# MCU_STM32F427ZGT6.net
KiCad netlist of a schematic drawn in Altium Designer
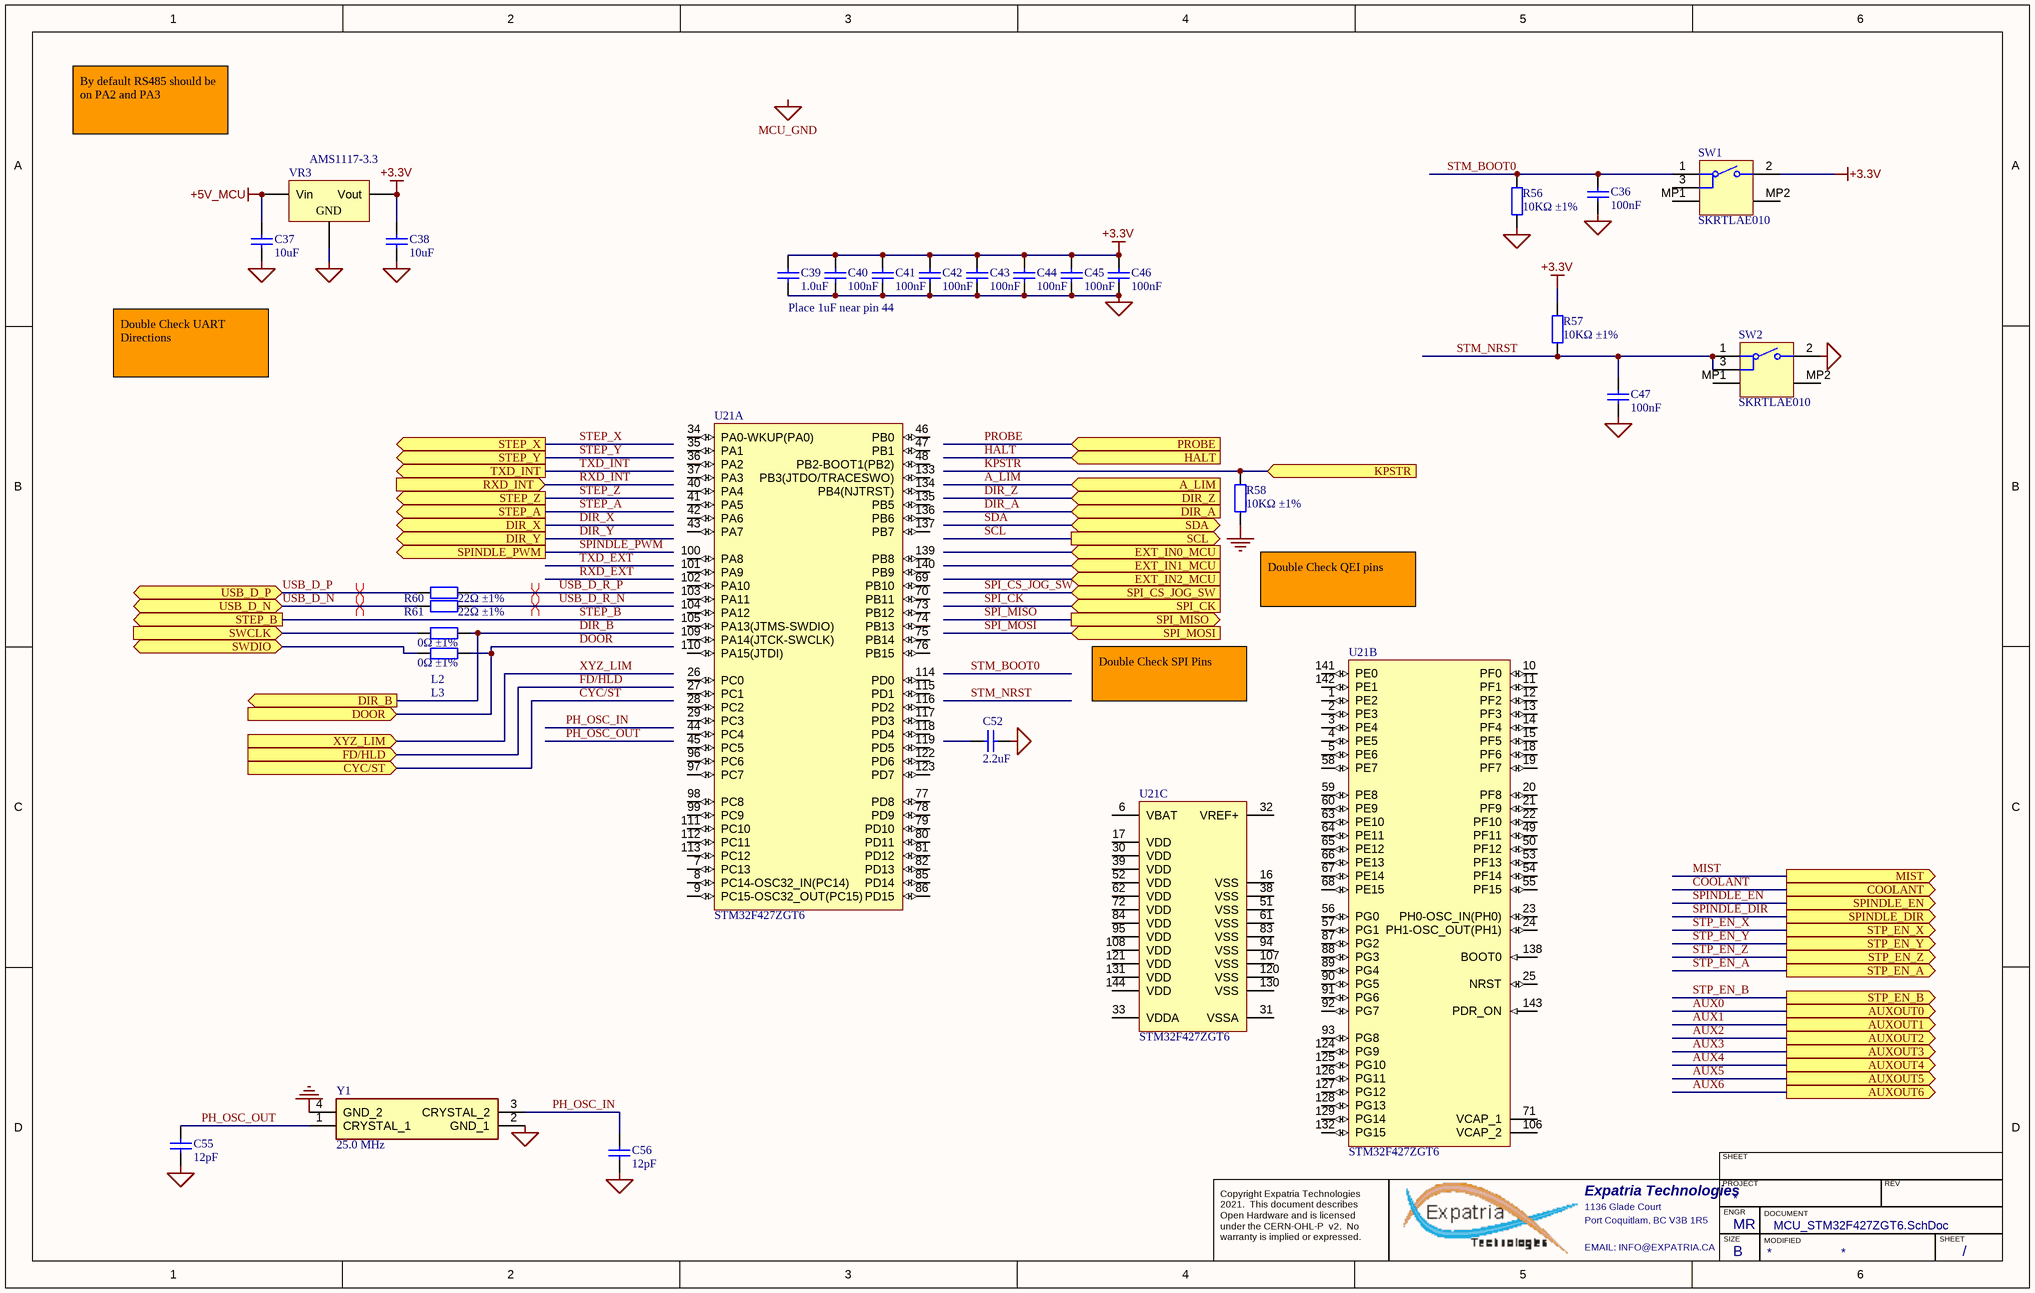
[diagram p0: MCU_STM32F427ZGT6.SchDoc]

(export (version "E")
  (design (tool "Eeschema 10.0.6"))
  (components
    (comp (ref "C36")
      (value "100nF")
      (footprint "0402_C")
      (description "Chip capacitors")
      (fields
        (field (name "MANUFACTURER") "Samsung Electro-Mechanics")
        (field (name "PARTNUMBER") "CL05B104KO5NNNC")
      )
      (libsource (lib "Cap") (part "0402 100nF (104) 10% 16V"))
    )
    (comp (ref "C37")
      (value "10uF")
      (footprint "1206_C")
      (description "Chip capacitors")
      (fields
        (field (name "MANUFACTURER") "Samsung Electro-Mechanics")
        (field (name "PARTNUMBER") "CL31A106KBHNNNE")
      )
      (libsource (lib "Cap") (part "1206 10uF (106) 10% 50V"))
    )
    (comp (ref "C38")
      (value "10uF")
      (footprint "1206_C")
      (description "Chip capacitors")
      (fields
        (field (name "MANUFACTURER") "Samsung Electro-Mechanics")
        (field (name "PARTNUMBER") "CL31A106KBHNNNE")
      )
      (libsource (lib "Cap") (part "1206 10uF (106) 10% 50V"))
    )
    (comp (ref "C39")
      (value "1.0uF")
      (footprint "0402_C")
      (description "Chip capacitor")
      (fields
        (field (name "MANUFACTURER") "Samsung Electro-Mechanics")
        (field (name "PARTNUMBER") "CL05A105KA5NQNC")
      )
      (libsource (lib "Cap") (part "0402 1.0uF (105) 10% 25V"))
    )
    (comp (ref "C40")
      (value "100nF")
      (footprint "0402_C")
      (description "Chip capacitors")
      (fields
        (field (name "MANUFACTURER") "Samsung Electro-Mechanics")
        (field (name "PARTNUMBER") "CL05B104KO5NNNC")
      )
      (libsource (lib "Cap") (part "0402 100nF (104) 10% 16V"))
    )
    (comp (ref "C41")
      (value "100nF")
      (footprint "0402_C")
      (description "Chip capacitors")
      (fields
        (field (name "MANUFACTURER") "Samsung Electro-Mechanics")
        (field (name "PARTNUMBER") "CL05B104KO5NNNC")
      )
      (libsource (lib "Cap") (part "0402 100nF (104) 10% 16V"))
    )
    (comp (ref "C42")
      (value "100nF")
      (footprint "0402_C")
      (description "Chip capacitors")
      (fields
        (field (name "MANUFACTURER") "Samsung Electro-Mechanics")
        (field (name "PARTNUMBER") "CL05B104KO5NNNC")
      )
      (libsource (lib "Cap") (part "0402 100nF (104) 10% 16V"))
    )
    (comp (ref "C43")
      (value "100nF")
      (footprint "0402_C")
      (description "Chip capacitors")
      (fields
        (field (name "MANUFACTURER") "Samsung Electro-Mechanics")
        (field (name "PARTNUMBER") "CL05B104KO5NNNC")
      )
      (libsource (lib "Cap") (part "0402 100nF (104) 10% 16V"))
    )
    (comp (ref "C44")
      (value "100nF")
      (footprint "0402_C")
      (description "Chip capacitors")
      (fields
        (field (name "MANUFACTURER") "Samsung Electro-Mechanics")
        (field (name "PARTNUMBER") "CL05B104KO5NNNC")
      )
      (libsource (lib "Cap") (part "0402 100nF (104) 10% 16V"))
    )
    (comp (ref "C45")
      (value "100nF")
      (footprint "0402_C")
      (description "Chip capacitors")
      (fields
        (field (name "MANUFACTURER") "Samsung Electro-Mechanics")
        (field (name "PARTNUMBER") "CL05B104KO5NNNC")
      )
      (libsource (lib "Cap") (part "0402 100nF (104) 10% 16V"))
    )
    (comp (ref "C46")
      (value "100nF")
      (footprint "0402_C")
      (description "Chip capacitors")
      (fields
        (field (name "MANUFACTURER") "Samsung Electro-Mechanics")
        (field (name "PARTNUMBER") "CL05B104KO5NNNC")
      )
      (libsource (lib "Cap") (part "0402 100nF (104) 10% 16V"))
    )
    (comp (ref "C47")
      (value "100nF")
      (footprint "0402_C")
      (description "Chip capacitors")
      (fields
        (field (name "MANUFACTURER") "Samsung Electro-Mechanics")
        (field (name "PARTNUMBER") "CL05B104KO5NNNC")
      )
      (libsource (lib "Cap") (part "0402 100nF (104) 10% 16V"))
    )
    (comp (ref "C52")
      (value "2.2uF")
      (footprint "0603_C")
      (description "Chip capacitors")
      (fields
        (field (name "MANUFACTURER") "Samsung Electro-Mechanics")
        (field (name "PARTNUMBER") "CL10A225KO8NNNC")
      )
      (libsource (lib "Cap") (part "0603 2.2uF (225) 10% 16V"))
    )
    (comp (ref "C55")
      (value "12pF")
      (footprint "0402_C")
      (description "Chip capacitors")
      (fields
        (field (name "MANUFACTURER") "Guangdong Fenghua Advanced Tech")
        (field (name "PARTNUMBER") "0402CG120J500NT")
      )
      (libsource (lib "Cap") (part "0402 12pF (120) 5% 50V"))
    )
    (comp (ref "C56")
      (value "12pF")
      (footprint "0402_C")
      (description "Chip capacitors")
      (fields
        (field (name "MANUFACTURER") "Guangdong Fenghua Advanced Tech")
        (field (name "PARTNUMBER") "0402CG120J500NT")
      )
      (libsource (lib "Cap") (part "0402 12pF (120) 5% 50V"))
    )
    (comp (ref "L2")
      (value "0Ω ±1%")
      (footprint "0402_R")
      (description "Chip resistor")
      (fields (field (name "POWER") "1/16W") (field (name "MANUFACTURER") "Uniroyal Elec"))
      (libsource (lib "PrintNC_GRBLHAL_Breakout") (part "0402 0R (0R0) 1%"))
    )
    (comp (ref "L3")
      (value "0Ω ±1%")
      (footprint "0402_R")
      (description "Chip resistor")
      (fields (field (name "POWER") "1/16W") (field (name "MANUFACTURER") "Uniroyal Elec"))
      (libsource (lib "PrintNC_GRBLHAL_Breakout") (part "0402 0R (0R0) 1%"))
    )
    (comp (ref "R56")
      (value "10KΩ ±1%")
      (footprint "0402_R")
      (description "Chip resistor")
      (fields (field (name "MANUFACTURER") "Uniroyal Elec") (field (name "PARTNUMBER") "0402WGF1002TCE"))
      (libsource (lib "RES") (part "0402 10K (1002) 1%"))
    )
    (comp (ref "R57")
      (value "10KΩ ±1%")
      (footprint "0402_R")
      (description "Chip resistor")
      (fields (field (name "MANUFACTURER") "Uniroyal Elec") (field (name "PARTNUMBER") "0402WGF1002TCE"))
      (libsource (lib "RES") (part "0402 10K (1002) 1%"))
    )
    (comp (ref "R58")
      (value "10KΩ ±1%")
      (footprint "0402_R")
      (description "Chip resistor")
      (fields (field (name "MANUFACTURER") "Uniroyal Elec") (field (name "PARTNUMBER") "0402WGF1002TCE"))
      (libsource (lib "") (part "0402 10K (1002) 1%_1"))
    )
    (comp (ref "R60")
      (value "22Ω ±1%")
      (footprint "0402_R")
      (description "Chip resistor")
      (fields (field (name "MANUFACTURER") "Uniroyal Elec") (field (name "PARTNUMBER") "0402WGF220JTCE"))
      (libsource (lib "RES") (part "0402 22R (22R0) 1%"))
    )
    (comp (ref "R61")
      (value "22Ω ±1%")
      (footprint "0402_R")
      (description "Chip resistor")
      (fields (field (name "MANUFACTURER") "Uniroyal Elec") (field (name "PARTNUMBER") "0402WGF220JTCE"))
      (libsource (lib "RES") (part "0402 22R (22R0) 1%"))
    )
    (comp (ref "SW1")
      (value "SKRTLAE010")
      (footprint "ALPS-SKRTLAE010_V")
      (description "Side Push Type, 250 V, -40 to 90 degC, 3-Pin SMD, RoHS, Tape and Reel")
      (fields (field (name "MANUFACTURER") "ALPS"))
      (libsource (lib "Altium Content Vault") (part "SW_SPST-3_A"))
    )
    (comp (ref "SW2")
      (value "SKRTLAE010")
      (footprint "ALPS-SKRTLAE010_V")
      (description "Side Push Type, 250 V, -40 to 90 degC, 3-Pin SMD, RoHS, Tape and Reel")
      (fields (field (name "MANUFACTURER") "ALPS"))
      (libsource (lib "Altium Content Vault") (part "SW_SPST-3_A"))
    )
    (comp (ref "U21")
      (value "STM32F427ZGT6")
      (footprint "STM-LQFP144_V")
      (fields (field (name "MANUFACTURER") "STMicroelectronics"))
      (libsource (lib "Altium Content Vault") (part "MC-ARM-STM32F427-SQ144"))
    )
    (comp (ref "VR3")
      (value "AMS1117-3.3")
      (footprint "SOT-223")
      (description "低压差线性稳压(LDO)")
      (libsource (lib "LDO") (part "SOT-223 AMS1117-3.3"))
    )
    (comp (ref "Y1")
      (value "25.0 MHz")
      (footprint "SamacSys:YSX321SL")
      (description "Crystal or Oscillator")
      (fields (field (name "MANUFACTURER_PART_NUMBER") "X322525MSB4SI"))
      (libsource (lib "*") (part "YSX321SL"))
    )
  )
  (nets
    (net (code "1") (name "+3.3V") (class "Default")
      (node (ref "C38") (pin "2") (pinfunction "2_2") (pintype "passive"))
      (node (ref "C39") (pin "2") (pinfunction "2_2") (pintype "passive"))
      (node (ref "C40") (pin "2") (pinfunction "2_2") (pintype "passive"))
      (node (ref "C41") (pin "2") (pinfunction "2_2") (pintype "passive"))
      (node (ref "C42") (pin "2") (pinfunction "2_2") (pintype "passive"))
      (node (ref "C43") (pin "2") (pinfunction "2_2") (pintype "passive"))
      (node (ref "C44") (pin "2") (pinfunction "2_2") (pintype "passive"))
      (node (ref "C45") (pin "2") (pinfunction "2_2") (pintype "passive"))
      (node (ref "C46") (pin "2") (pinfunction "2_2") (pintype "passive"))
      (node (ref "R57") (pin "1") (pinfunction "1_1") (pintype "passive"))
      (node (ref "SW1") (pin "2") (pinfunction "2_2") (pintype "passive"))
      (node (ref "VR3") (pin "2") (pinfunction "Vout_2") (pintype "passive"))
    )
    (net (code "2") (name "+5V_MCU") (class "Default")
      (node (ref "C37") (pin "2") (pinfunction "2_2") (pintype "passive"))
      (node (ref "VR3") (pin "3") (pinfunction "Vin_3") (pintype "passive"))
    )
    (net (code "14") (name "/DIR_B") (class "Default")
      (node (ref "L2") (pin "2") (pinfunction "2_2") (pintype "passive"))
    )
    (net (code "18") (name "/DOOR") (class "Default")
      (node (ref "L3") (pin "2") (pinfunction "2_2") (pintype "passive"))
    )
    (net (code "24") (name "/KPSTR") (class "Default")
      (node (ref "R58") (pin "2") (pinfunction "2_2") (pintype "passive"))
    )
    (net (code "26") (name "/PH_OSC_IN") (class "Default")
      (node (ref "C56") (pin "2") (pinfunction "2_2") (pintype "passive"))
      (node (ref "Y1") (pin "3") (pinfunction "CRYSTAL_2_3") (pintype "passive"))
    )
    (net (code "27") (name "/PH_OSC_OUT") (class "Default")
      (node (ref "C55") (pin "2") (pinfunction "2_2") (pintype "passive"))
      (node (ref "Y1") (pin "1") (pinfunction "CRYSTAL_1_1") (pintype "passive"))
    )
    (net (code "45") (name "/STM_BOOT0") (class "Default")
      (node (ref "C36") (pin "2") (pinfunction "2_2") (pintype "passive"))
      (node (ref "R56") (pin "1") (pinfunction "1_1") (pintype "passive"))
      (node (ref "SW1") (pin "1") (pinfunction "1_1") (pintype "passive"))
    )
    (net (code "46") (name "/STM_NRST") (class "Default")
      (node (ref "C47") (pin "2") (pinfunction "2_2") (pintype "passive"))
      (node (ref "R57") (pin "2") (pinfunction "2_2") (pintype "passive"))
      (node (ref "SW2") (pin "1") (pinfunction "1_1") (pintype "passive"))
      (node (ref "SW2") (pin "3") (pinfunction "3_3") (pintype "passive"))
    )
    (net (code "52") (name "/SWCLK") (class "Default")
      (node (ref "L2") (pin "1") (pinfunction "1_1") (pintype "passive"))
    )
    (net (code "53") (name "/SWDIO") (class "Default")
      (node (ref "L3") (pin "1") (pinfunction "1_1") (pintype "passive"))
    )
    (net (code "56") (name "/USB_D_N") (class "Default")
      (node (ref "R61") (pin "2") (pinfunction "2_2") (pintype "passive"))
    )
    (net (code "57") (name "/USB_D_P") (class "Default")
      (node (ref "R60") (pin "2") (pinfunction "2_2") (pintype "passive"))
    )
    (net (code "58") (name "/USB_D_R_N") (class "Default")
      (node (ref "R61") (pin "1") (pinfunction "1_1") (pintype "passive"))
    )
    (net (code "59") (name "/USB_D_R_P") (class "Default")
      (node (ref "R60") (pin "1") (pinfunction "1_1") (pintype "passive"))
    )
    (net (code "61") (name "GND") (class "Default")
      (node (ref "R58") (pin "1") (pinfunction "1_1") (pintype "passive"))
      (node (ref "Y1") (pin "4") (pinfunction "GND_2_4") (pintype "passive"))
    )
    (net (code "62") (name "MCU_GND") (class "Default")
      (node (ref "C36") (pin "1") (pinfunction "1_1") (pintype "passive"))
      (node (ref "C37") (pin "1") (pinfunction "1_1") (pintype "passive"))
      (node (ref "C38") (pin "1") (pinfunction "1_1") (pintype "passive"))
      (node (ref "C39") (pin "1") (pinfunction "1_1") (pintype "passive"))
      (node (ref "C40") (pin "1") (pinfunction "1_1") (pintype "passive"))
      (node (ref "C41") (pin "1") (pinfunction "1_1") (pintype "passive"))
      (node (ref "C42") (pin "1") (pinfunction "1_1") (pintype "passive"))
      (node (ref "C43") (pin "1") (pinfunction "1_1") (pintype "passive"))
      (node (ref "C44") (pin "1") (pinfunction "1_1") (pintype "passive"))
      (node (ref "C45") (pin "1") (pinfunction "1_1") (pintype "passive"))
      (node (ref "C46") (pin "1") (pinfunction "1_1") (pintype "passive"))
      (node (ref "C47") (pin "1") (pinfunction "1_1") (pintype "passive"))
      (node (ref "C52") (pin "1") (pinfunction "1_1") (pintype "passive"))
      (node (ref "C55") (pin "1") (pinfunction "1_1") (pintype "passive"))
      (node (ref "C56") (pin "1") (pinfunction "1_1") (pintype "passive"))
      (node (ref "R56") (pin "2") (pinfunction "2_2") (pintype "passive"))
      (node (ref "SW2") (pin "2") (pinfunction "2_2") (pintype "passive"))
      (node (ref "VR3") (pin "1") (pinfunction "GND_1") (pintype "passive"))
      (node (ref "Y1") (pin "2") (pinfunction "GND_1_2") (pintype "passive"))
    )
    (net (code "63") (name "unconnected-(C52-Pad2)") (class "Default")
      (node (ref "C52") (pin "2") (pinfunction "2_2") (pintype "passive"))
    )
    (net (code "64") (name "unconnected-(SW1-Pad3)") (class "Default")
      (node (ref "SW1") (pin "3") (pinfunction "3_3") (pintype "passive"))
    )
    (net (code "65") (name "unconnected-(SW1-PadMP1)") (class "Default")
      (node (ref "SW1") (pin "MP1") (pinfunction "MP1_MP1") (pintype "passive"))
    )
    (net (code "66") (name "unconnected-(SW1-PadMP2)") (class "Default")
      (node (ref "SW1") (pin "MP2") (pinfunction "MP2_MP2") (pintype "passive"))
    )
    (net (code "67") (name "unconnected-(SW2-PadMP1)") (class "Default")
      (node (ref "SW2") (pin "MP1") (pinfunction "MP1_MP1") (pintype "passive"))
    )
    (net (code "68") (name "unconnected-(SW2-PadMP2)") (class "Default")
      (node (ref "SW2") (pin "MP2") (pinfunction "MP2_MP2") (pintype "passive"))
    )
    (net (code "69") (name "unconnected-(U21A-PA0-WKUP(PA0)-Pad34)") (class "Default")
      (node (ref "U21") (pin "34") (pinfunction "PA0-WKUP(PA0)_34") (pintype "bidirectional"))
    )
    (net (code "70") (name "unconnected-(U21A-PA1-Pad35)") (class "Default")
      (node (ref "U21") (pin "35") (pinfunction "PA1_35") (pintype "bidirectional"))
    )
    (net (code "71") (name "unconnected-(U21A-PA2-Pad36)") (class "Default")
      (node (ref "U21") (pin "36") (pinfunction "PA2_36") (pintype "bidirectional"))
    )
    (net (code "72") (name "unconnected-(U21A-PA3-Pad37)") (class "Default")
      (node (ref "U21") (pin "37") (pinfunction "PA3_37") (pintype "bidirectional"))
    )
    (net (code "73") (name "unconnected-(U21A-PA4-Pad40)") (class "Default")
      (node (ref "U21") (pin "40") (pinfunction "PA4_40") (pintype "bidirectional"))
    )
    (net (code "74") (name "unconnected-(U21A-PA5-Pad41)") (class "Default")
      (node (ref "U21") (pin "41") (pinfunction "PA5_41") (pintype "bidirectional"))
    )
    (net (code "75") (name "unconnected-(U21A-PA6-Pad42)") (class "Default")
      (node (ref "U21") (pin "42") (pinfunction "PA6_42") (pintype "bidirectional"))
    )
    (net (code "76") (name "unconnected-(U21A-PA7-Pad43)") (class "Default")
      (node (ref "U21") (pin "43") (pinfunction "PA7_43") (pintype "bidirectional"))
    )
    (net (code "77") (name "unconnected-(U21A-PA8-Pad100)") (class "Default")
      (node (ref "U21") (pin "100") (pinfunction "PA8_100") (pintype "bidirectional"))
    )
    (net (code "78") (name "unconnected-(U21A-PA9-Pad101)") (class "Default")
      (node (ref "U21") (pin "101") (pinfunction "PA9_101") (pintype "bidirectional"))
    )
    (net (code "79") (name "unconnected-(U21A-PA10-Pad102)") (class "Default")
      (node (ref "U21") (pin "102") (pinfunction "PA10_102") (pintype "bidirectional"))
    )
    (net (code "80") (name "unconnected-(U21A-PA11-Pad103)") (class "Default")
      (node (ref "U21") (pin "103") (pinfunction "PA11_103") (pintype "bidirectional"))
    )
    (net (code "81") (name "unconnected-(U21A-PA12-Pad104)") (class "Default")
      (node (ref "U21") (pin "104") (pinfunction "PA12_104") (pintype "bidirectional"))
    )
    (net (code "82") (name "unconnected-(U21A-PA13(JTMS-SWDIO)-Pad105)") (class "Default")
      (node (ref "U21") (pin "105") (pinfunction "PA13(JTMS-SWDIO)_105") (pintype "bidirectional"))
    )
    (net (code "83") (name "unconnected-(U21A-PA14(JTCK-SWCLK)-Pad109)") (class "Default")
      (node (ref "U21") (pin "109") (pinfunction "PA14(JTCK-SWCLK)_109") (pintype "bidirectional"))
    )
    (net (code "84") (name "unconnected-(U21A-PA15(JTDI)-Pad110)") (class "Default")
      (node (ref "U21") (pin "110") (pinfunction "PA15(JTDI)_110") (pintype "bidirectional"))
    )
    (net (code "85") (name "unconnected-(U21A-PB0-Pad46)") (class "Default")
      (node (ref "U21") (pin "46") (pinfunction "PB0_46") (pintype "bidirectional"))
    )
    (net (code "86") (name "unconnected-(U21A-PB1-Pad47)") (class "Default")
      (node (ref "U21") (pin "47") (pinfunction "PB1_47") (pintype "bidirectional"))
    )
    (net (code "87") (name "unconnected-(U21A-PB2-BOOT1(PB2)-Pad48)") (class "Default")
      (node (ref "U21") (pin "48") (pinfunction "PB2-BOOT1(PB2)_48") (pintype "bidirectional"))
    )
    (net (code "88") (name "unconnected-(U21A-PB3(JTDO{slash}TRACESWO)-Pad133)") (class "Default")
      (node (ref "U21") (pin "133") (pinfunction "PB3(JTDO/TRACESWO)_133") (pintype "bidirectional"))
    )
    (net (code "89") (name "unconnected-(U21A-PB4(NJTRST)-Pad134)") (class "Default")
      (node (ref "U21") (pin "134") (pinfunction "PB4(NJTRST)_134") (pintype "bidirectional"))
    )
    (net (code "90") (name "unconnected-(U21A-PB5-Pad135)") (class "Default")
      (node (ref "U21") (pin "135") (pinfunction "PB5_135") (pintype "bidirectional"))
    )
    (net (code "91") (name "unconnected-(U21A-PB6-Pad136)") (class "Default")
      (node (ref "U21") (pin "136") (pinfunction "PB6_136") (pintype "bidirectional"))
    )
    (net (code "92") (name "unconnected-(U21A-PB7-Pad137)") (class "Default")
      (node (ref "U21") (pin "137") (pinfunction "PB7_137") (pintype "bidirectional"))
    )
    (net (code "93") (name "unconnected-(U21A-PB8-Pad139)") (class "Default")
      (node (ref "U21") (pin "139") (pinfunction "PB8_139") (pintype "bidirectional"))
    )
    (net (code "94") (name "unconnected-(U21A-PB9-Pad140)") (class "Default")
      (node (ref "U21") (pin "140") (pinfunction "PB9_140") (pintype "bidirectional"))
    )
    (net (code "95") (name "unconnected-(U21A-PB10-Pad69)") (class "Default")
      (node (ref "U21") (pin "69") (pinfunction "PB10_69") (pintype "bidirectional"))
    )
    (net (code "96") (name "unconnected-(U21A-PB11-Pad70)") (class "Default")
      (node (ref "U21") (pin "70") (pinfunction "PB11_70") (pintype "bidirectional"))
    )
    (net (code "97") (name "unconnected-(U21A-PB12-Pad73)") (class "Default")
      (node (ref "U21") (pin "73") (pinfunction "PB12_73") (pintype "bidirectional"))
    )
    (net (code "98") (name "unconnected-(U21A-PB13-Pad74)") (class "Default")
      (node (ref "U21") (pin "74") (pinfunction "PB13_74") (pintype "bidirectional"))
    )
    (net (code "99") (name "unconnected-(U21A-PB14-Pad75)") (class "Default")
      (node (ref "U21") (pin "75") (pinfunction "PB14_75") (pintype "bidirectional"))
    )
    (net (code "100") (name "unconnected-(U21A-PB15-Pad76)") (class "Default")
      (node (ref "U21") (pin "76") (pinfunction "PB15_76") (pintype "bidirectional"))
    )
    (net (code "101") (name "unconnected-(U21A-PC0-Pad26)") (class "Default")
      (node (ref "U21") (pin "26") (pinfunction "PC0_26") (pintype "bidirectional"))
    )
    (net (code "102") (name "unconnected-(U21A-PC1-Pad27)") (class "Default")
      (node (ref "U21") (pin "27") (pinfunction "PC1_27") (pintype "bidirectional"))
    )
    (net (code "103") (name "unconnected-(U21A-PC2-Pad28)") (class "Default")
      (node (ref "U21") (pin "28") (pinfunction "PC2_28") (pintype "bidirectional"))
    )
    (net (code "104") (name "unconnected-(U21A-PC3-Pad29)") (class "Default")
      (node (ref "U21") (pin "29") (pinfunction "PC3_29") (pintype "bidirectional"))
    )
    (net (code "105") (name "unconnected-(U21A-PC4-Pad44)") (class "Default")
      (node (ref "U21") (pin "44") (pinfunction "PC4_44") (pintype "bidirectional"))
    )
    (net (code "106") (name "unconnected-(U21A-PC5-Pad45)") (class "Default")
      (node (ref "U21") (pin "45") (pinfunction "PC5_45") (pintype "bidirectional"))
    )
    (net (code "107") (name "unconnected-(U21A-PC6-Pad96)") (class "Default")
      (node (ref "U21") (pin "96") (pinfunction "PC6_96") (pintype "bidirectional"))
    )
    (net (code "108") (name "unconnected-(U21A-PC7-Pad97)") (class "Default")
      (node (ref "U21") (pin "97") (pinfunction "PC7_97") (pintype "bidirectional"))
    )
    (net (code "109") (name "unconnected-(U21A-PC8-Pad98)") (class "Default")
      (node (ref "U21") (pin "98") (pinfunction "PC8_98") (pintype "bidirectional"))
    )
    (net (code "110") (name "unconnected-(U21A-PC9-Pad99)") (class "Default")
      (node (ref "U21") (pin "99") (pinfunction "PC9_99") (pintype "bidirectional"))
    )
    (net (code "111") (name "unconnected-(U21A-PC10-Pad111)") (class "Default")
      (node (ref "U21") (pin "111") (pinfunction "PC10_111") (pintype "bidirectional"))
    )
    (net (code "112") (name "unconnected-(U21A-PC11-Pad112)") (class "Default")
      (node (ref "U21") (pin "112") (pinfunction "PC11_112") (pintype "bidirectional"))
    )
    (net (code "113") (name "unconnected-(U21A-PC12-Pad113)") (class "Default")
      (node (ref "U21") (pin "113") (pinfunction "PC12_113") (pintype "bidirectional"))
    )
    (net (code "114") (name "unconnected-(U21A-PC13-Pad7)") (class "Default")
      (node (ref "U21") (pin "7") (pinfunction "PC13_7") (pintype "bidirectional"))
    )
    (net (code "115") (name "unconnected-(U21A-PC14-OSC32_IN(PC14)-Pad8)") (class "Default")
      (node (ref "U21") (pin "8") (pinfunction "PC14-OSC32_IN(PC14)_8") (pintype "bidirectional"))
    )
    (net (code "116") (name "unconnected-(U21A-PC15-OSC32_OUT(PC15)-Pad9)") (class "Default")
      (node (ref "U21") (pin "9") (pinfunction "PC15-OSC32_OUT(PC15)_9") (pintype "bidirectional"))
    )
    (net (code "117") (name "unconnected-(U21A-PD0-Pad114)") (class "Default")
      (node (ref "U21") (pin "114") (pinfunction "PD0_114") (pintype "bidirectional"))
    )
    (net (code "118") (name "unconnected-(U21A-PD1-Pad115)") (class "Default")
      (node (ref "U21") (pin "115") (pinfunction "PD1_115") (pintype "bidirectional"))
    )
    (net (code "119") (name "unconnected-(U21A-PD2-Pad116)") (class "Default")
      (node (ref "U21") (pin "116") (pinfunction "PD2_116") (pintype "bidirectional"))
    )
    (net (code "120") (name "unconnected-(U21A-PD3-Pad117)") (class "Default")
      (node (ref "U21") (pin "117") (pinfunction "PD3_117") (pintype "bidirectional"))
    )
    (net (code "121") (name "unconnected-(U21A-PD4-Pad118)") (class "Default")
      (node (ref "U21") (pin "118") (pinfunction "PD4_118") (pintype "bidirectional"))
    )
    (net (code "122") (name "unconnected-(U21A-PD5-Pad119)") (class "Default")
      (node (ref "U21") (pin "119") (pinfunction "PD5_119") (pintype "bidirectional"))
    )
    (net (code "123") (name "unconnected-(U21A-PD6-Pad122)") (class "Default")
      (node (ref "U21") (pin "122") (pinfunction "PD6_122") (pintype "bidirectional"))
    )
    (net (code "124") (name "unconnected-(U21A-PD7-Pad123)") (class "Default")
      (node (ref "U21") (pin "123") (pinfunction "PD7_123") (pintype "bidirectional"))
    )
    (net (code "125") (name "unconnected-(U21A-PD8-Pad77)") (class "Default")
      (node (ref "U21") (pin "77") (pinfunction "PD8_77") (pintype "bidirectional"))
    )
    (net (code "126") (name "unconnected-(U21A-PD9-Pad78)") (class "Default")
      (node (ref "U21") (pin "78") (pinfunction "PD9_78") (pintype "bidirectional"))
    )
    (net (code "127") (name "unconnected-(U21A-PD10-Pad79)") (class "Default")
      (node (ref "U21") (pin "79") (pinfunction "PD10_79") (pintype "bidirectional"))
    )
    (net (code "128") (name "unconnected-(U21A-PD11-Pad80)") (class "Default")
      (node (ref "U21") (pin "80") (pinfunction "PD11_80") (pintype "bidirectional"))
    )
    (net (code "129") (name "unconnected-(U21A-PD12-Pad81)") (class "Default")
      (node (ref "U21") (pin "81") (pinfunction "PD12_81") (pintype "bidirectional"))
    )
    (net (code "130") (name "unconnected-(U21A-PD13-Pad82)") (class "Default")
      (node (ref "U21") (pin "82") (pinfunction "PD13_82") (pintype "bidirectional"))
    )
    (net (code "131") (name "unconnected-(U21A-PD14-Pad85)") (class "Default")
      (node (ref "U21") (pin "85") (pinfunction "PD14_85") (pintype "bidirectional"))
    )
    (net (code "132") (name "unconnected-(U21A-PD15-Pad86)") (class "Default")
      (node (ref "U21") (pin "86") (pinfunction "PD15_86") (pintype "bidirectional"))
    )
    (net (code "133") (name "unconnected-(U21B-BOOT0-Pad138)") (class "Default")
      (node (ref "U21") (pin "138") (pinfunction "BOOT0_138") (pintype "input"))
    )
    (net (code "134") (name "unconnected-(U21B-NRST-Pad25)") (class "Default")
      (node (ref "U21") (pin "25") (pinfunction "NRST_25") (pintype "bidirectional"))
    )
    (net (code "135") (name "unconnected-(U21B-PDR_ON-Pad143)") (class "Default")
      (node (ref "U21") (pin "143") (pinfunction "PDR_ON_143") (pintype "input"))
    )
    (net (code "136") (name "unconnected-(U21B-PE0-Pad141)") (class "Default")
      (node (ref "U21") (pin "141") (pinfunction "PE0_141") (pintype "bidirectional"))
    )
    (net (code "137") (name "unconnected-(U21B-PE1-Pad142)") (class "Default")
      (node (ref "U21") (pin "142") (pinfunction "PE1_142") (pintype "bidirectional"))
    )
    (net (code "138") (name "unconnected-(U21B-PE2-Pad1)") (class "Default")
      (node (ref "U21") (pin "1") (pinfunction "PE2_1") (pintype "bidirectional"))
    )
    (net (code "139") (name "unconnected-(U21B-PE3-Pad2)") (class "Default")
      (node (ref "U21") (pin "2") (pinfunction "PE3_2") (pintype "bidirectional"))
    )
    (net (code "140") (name "unconnected-(U21B-PE4-Pad3)") (class "Default")
      (node (ref "U21") (pin "3") (pinfunction "PE4_3") (pintype "bidirectional"))
    )
    (net (code "141") (name "unconnected-(U21B-PE5-Pad4)") (class "Default")
      (node (ref "U21") (pin "4") (pinfunction "PE5_4") (pintype "bidirectional"))
    )
    (net (code "142") (name "unconnected-(U21B-PE6-Pad5)") (class "Default")
      (node (ref "U21") (pin "5") (pinfunction "PE6_5") (pintype "bidirectional"))
    )
    (net (code "143") (name "unconnected-(U21B-PE7-Pad58)") (class "Default")
      (node (ref "U21") (pin "58") (pinfunction "PE7_58") (pintype "bidirectional"))
    )
    (net (code "144") (name "unconnected-(U21B-PE8-Pad59)") (class "Default")
      (node (ref "U21") (pin "59") (pinfunction "PE8_59") (pintype "bidirectional"))
    )
    (net (code "145") (name "unconnected-(U21B-PE9-Pad60)") (class "Default")
      (node (ref "U21") (pin "60") (pinfunction "PE9_60") (pintype "bidirectional"))
    )
    (net (code "146") (name "unconnected-(U21B-PE10-Pad63)") (class "Default")
      (node (ref "U21") (pin "63") (pinfunction "PE10_63") (pintype "bidirectional"))
    )
    (net (code "147") (name "unconnected-(U21B-PE11-Pad64)") (class "Default")
      (node (ref "U21") (pin "64") (pinfunction "PE11_64") (pintype "bidirectional"))
    )
    (net (code "148") (name "unconnected-(U21B-PE12-Pad65)") (class "Default")
      (node (ref "U21") (pin "65") (pinfunction "PE12_65") (pintype "bidirectional"))
    )
    (net (code "149") (name "unconnected-(U21B-PE13-Pad66)") (class "Default")
      (node (ref "U21") (pin "66") (pinfunction "PE13_66") (pintype "bidirectional"))
    )
    (net (code "150") (name "unconnected-(U21B-PE14-Pad67)") (class "Default")
      (node (ref "U21") (pin "67") (pinfunction "PE14_67") (pintype "bidirectional"))
    )
    (net (code "151") (name "unconnected-(U21B-PE15-Pad68)") (class "Default")
      (node (ref "U21") (pin "68") (pinfunction "PE15_68") (pintype "bidirectional"))
    )
    (net (code "152") (name "unconnected-(U21B-PF0-Pad10)") (class "Default")
      (node (ref "U21") (pin "10") (pinfunction "PF0_10") (pintype "bidirectional"))
    )
    (net (code "153") (name "unconnected-(U21B-PF1-Pad11)") (class "Default")
      (node (ref "U21") (pin "11") (pinfunction "PF1_11") (pintype "bidirectional"))
    )
    (net (code "154") (name "unconnected-(U21B-PF2-Pad12)") (class "Default")
      (node (ref "U21") (pin "12") (pinfunction "PF2_12") (pintype "bidirectional"))
    )
    (net (code "155") (name "unconnected-(U21B-PF3-Pad13)") (class "Default")
      (node (ref "U21") (pin "13") (pinfunction "PF3_13") (pintype "bidirectional"))
    )
    (net (code "156") (name "unconnected-(U21B-PF4-Pad14)") (class "Default")
      (node (ref "U21") (pin "14") (pinfunction "PF4_14") (pintype "bidirectional"))
    )
    (net (code "157") (name "unconnected-(U21B-PF5-Pad15)") (class "Default")
      (node (ref "U21") (pin "15") (pinfunction "PF5_15") (pintype "bidirectional"))
    )
    (net (code "158") (name "unconnected-(U21B-PF6-Pad18)") (class "Default")
      (node (ref "U21") (pin "18") (pinfunction "PF6_18") (pintype "bidirectional"))
    )
    (net (code "159") (name "unconnected-(U21B-PF7-Pad19)") (class "Default")
      (node (ref "U21") (pin "19") (pinfunction "PF7_19") (pintype "bidirectional"))
    )
    (net (code "160") (name "unconnected-(U21B-PF8-Pad20)") (class "Default")
      (node (ref "U21") (pin "20") (pinfunction "PF8_20") (pintype "bidirectional"))
    )
    (net (code "161") (name "unconnected-(U21B-PF9-Pad21)") (class "Default")
      (node (ref "U21") (pin "21") (pinfunction "PF9_21") (pintype "bidirectional"))
    )
    (net (code "162") (name "unconnected-(U21B-PF10-Pad22)") (class "Default")
      (node (ref "U21") (pin "22") (pinfunction "PF10_22") (pintype "bidirectional"))
    )
    (net (code "163") (name "unconnected-(U21B-PF11-Pad49)") (class "Default")
      (node (ref "U21") (pin "49") (pinfunction "PF11_49") (pintype "bidirectional"))
    )
    (net (code "164") (name "unconnected-(U21B-PF12-Pad50)") (class "Default")
      (node (ref "U21") (pin "50") (pinfunction "PF12_50") (pintype "bidirectional"))
    )
    (net (code "165") (name "unconnected-(U21B-PF13-Pad53)") (class "Default")
      (node (ref "U21") (pin "53") (pinfunction "PF13_53") (pintype "bidirectional"))
    )
    (net (code "166") (name "unconnected-(U21B-PF14-Pad54)") (class "Default")
      (node (ref "U21") (pin "54") (pinfunction "PF14_54") (pintype "bidirectional"))
    )
    (net (code "167") (name "unconnected-(U21B-PF15-Pad55)") (class "Default")
      (node (ref "U21") (pin "55") (pinfunction "PF15_55") (pintype "bidirectional"))
    )
    (net (code "168") (name "unconnected-(U21B-PG0-Pad56)") (class "Default")
      (node (ref "U21") (pin "56") (pinfunction "PG0_56") (pintype "bidirectional"))
    )
    (net (code "169") (name "unconnected-(U21B-PG1-Pad57)") (class "Default")
      (node (ref "U21") (pin "57") (pinfunction "PG1_57") (pintype "bidirectional"))
    )
    (net (code "170") (name "unconnected-(U21B-PG2-Pad87)") (class "Default")
      (node (ref "U21") (pin "87") (pinfunction "PG2_87") (pintype "bidirectional"))
    )
    (net (code "171") (name "unconnected-(U21B-PG3-Pad88)") (class "Default")
      (node (ref "U21") (pin "88") (pinfunction "PG3_88") (pintype "bidirectional"))
    )
    (net (code "172") (name "unconnected-(U21B-PG4-Pad89)") (class "Default")
      (node (ref "U21") (pin "89") (pinfunction "PG4_89") (pintype "bidirectional"))
    )
    (net (code "173") (name "unconnected-(U21B-PG5-Pad90)") (class "Default")
      (node (ref "U21") (pin "90") (pinfunction "PG5_90") (pintype "bidirectional"))
    )
    (net (code "174") (name "unconnected-(U21B-PG6-Pad91)") (class "Default")
      (node (ref "U21") (pin "91") (pinfunction "PG6_91") (pintype "bidirectional"))
    )
    (net (code "175") (name "unconnected-(U21B-PG7-Pad92)") (class "Default")
      (node (ref "U21") (pin "92") (pinfunction "PG7_92") (pintype "bidirectional"))
    )
    (net (code "176") (name "unconnected-(U21B-PG8-Pad93)") (class "Default")
      (node (ref "U21") (pin "93") (pinfunction "PG8_93") (pintype "bidirectional"))
    )
    (net (code "177") (name "unconnected-(U21B-PG9-Pad124)") (class "Default")
      (node (ref "U21") (pin "124") (pinfunction "PG9_124") (pintype "bidirectional"))
    )
    (net (code "178") (name "unconnected-(U21B-PG10-Pad125)") (class "Default")
      (node (ref "U21") (pin "125") (pinfunction "PG10_125") (pintype "bidirectional"))
    )
    (net (code "179") (name "unconnected-(U21B-PG11-Pad126)") (class "Default")
      (node (ref "U21") (pin "126") (pinfunction "PG11_126") (pintype "bidirectional"))
    )
    (net (code "180") (name "unconnected-(U21B-PG12-Pad127)") (class "Default")
      (node (ref "U21") (pin "127") (pinfunction "PG12_127") (pintype "bidirectional"))
    )
    (net (code "181") (name "unconnected-(U21B-PG13-Pad128)") (class "Default")
      (node (ref "U21") (pin "128") (pinfunction "PG13_128") (pintype "bidirectional"))
    )
    (net (code "182") (name "unconnected-(U21B-PG14-Pad129)") (class "Default")
      (node (ref "U21") (pin "129") (pinfunction "PG14_129") (pintype "bidirectional"))
    )
    (net (code "183") (name "unconnected-(U21B-PG15-Pad132)") (class "Default")
      (node (ref "U21") (pin "132") (pinfunction "PG15_132") (pintype "bidirectional"))
    )
    (net (code "184") (name "unconnected-(U21B-PH0-OSC_IN(PH0)-Pad23)") (class "Default")
      (node (ref "U21") (pin "23") (pinfunction "PH0-OSC_IN(PH0)_23") (pintype "bidirectional"))
    )
    (net (code "185") (name "unconnected-(U21B-PH1-OSC_OUT(PH1)-Pad24)") (class "Default")
      (node (ref "U21") (pin "24") (pinfunction "PH1-OSC_OUT(PH1)_24") (pintype "bidirectional"))
    )
    (net (code "186") (name "unconnected-(U21B-VCAP_1-Pad71)") (class "Default")
      (node (ref "U21") (pin "71") (pinfunction "VCAP_1_71") (pintype "power_in"))
    )
    (net (code "187") (name "unconnected-(U21B-VCAP_2-Pad106)") (class "Default")
      (node (ref "U21") (pin "106") (pinfunction "VCAP_2_106") (pintype "power_in"))
    )
    (net (code "188") (name "unconnected-(U21C-VBAT-Pad6)") (class "Default")
      (node (ref "U21") (pin "6") (pinfunction "VBAT_6") (pintype "power_in"))
    )
    (net (code "189") (name "unconnected-(U21C-VDD-Pad17)") (class "Default")
      (node (ref "U21") (pin "17") (pinfunction "VDD_17") (pintype "power_in"))
    )
    (net (code "190") (name "unconnected-(U21C-VDD-Pad30)") (class "Default")
      (node (ref "U21") (pin "30") (pinfunction "VDD_30") (pintype "power_in"))
    )
    (net (code "191") (name "unconnected-(U21C-VDD-Pad39)") (class "Default")
      (node (ref "U21") (pin "39") (pinfunction "VDD_39") (pintype "power_in"))
    )
    (net (code "192") (name "unconnected-(U21C-VDD-Pad52)") (class "Default")
      (node (ref "U21") (pin "52") (pinfunction "VDD_52") (pintype "power_in"))
    )
    (net (code "193") (name "unconnected-(U21C-VDD-Pad62)") (class "Default")
      (node (ref "U21") (pin "62") (pinfunction "VDD_62") (pintype "power_in"))
    )
    (net (code "194") (name "unconnected-(U21C-VDD-Pad72)") (class "Default")
      (node (ref "U21") (pin "72") (pinfunction "VDD_72") (pintype "power_in"))
    )
    (net (code "195") (name "unconnected-(U21C-VDD-Pad84)") (class "Default")
      (node (ref "U21") (pin "84") (pinfunction "VDD_84") (pintype "power_in"))
    )
    (net (code "196") (name "unconnected-(U21C-VDD-Pad95)") (class "Default")
      (node (ref "U21") (pin "95") (pinfunction "VDD_95") (pintype "power_in"))
    )
    (net (code "197") (name "unconnected-(U21C-VDD-Pad108)") (class "Default")
      (node (ref "U21") (pin "108") (pinfunction "VDD_108") (pintype "power_in"))
    )
    (net (code "198") (name "unconnected-(U21C-VDD-Pad121)") (class "Default")
      (node (ref "U21") (pin "121") (pinfunction "VDD_121") (pintype "power_in"))
    )
    (net (code "199") (name "unconnected-(U21C-VDD-Pad131)") (class "Default")
      (node (ref "U21") (pin "131") (pinfunction "VDD_131") (pintype "power_in"))
    )
    (net (code "200") (name "unconnected-(U21C-VDD-Pad144)") (class "Default")
      (node (ref "U21") (pin "144") (pinfunction "VDD_144") (pintype "power_in"))
    )
    (net (code "201") (name "unconnected-(U21C-VDDA-Pad33)") (class "Default")
      (node (ref "U21") (pin "33") (pinfunction "VDDA_33") (pintype "power_in"))
    )
    (net (code "202") (name "unconnected-(U21C-VREF+-Pad32)") (class "Default")
      (node (ref "U21") (pin "32") (pinfunction "VREF+_32") (pintype "power_in"))
    )
    (net (code "203") (name "unconnected-(U21C-VSS-Pad16)") (class "Default")
      (node (ref "U21") (pin "16") (pinfunction "VSS_16") (pintype "power_in"))
    )
    (net (code "204") (name "unconnected-(U21C-VSS-Pad38)") (class "Default")
      (node (ref "U21") (pin "38") (pinfunction "VSS_38") (pintype "power_in"))
    )
    (net (code "205") (name "unconnected-(U21C-VSS-Pad51)") (class "Default")
      (node (ref "U21") (pin "51") (pinfunction "VSS_51") (pintype "power_in"))
    )
    (net (code "206") (name "unconnected-(U21C-VSS-Pad61)") (class "Default")
      (node (ref "U21") (pin "61") (pinfunction "VSS_61") (pintype "power_in"))
    )
    (net (code "207") (name "unconnected-(U21C-VSS-Pad83)") (class "Default")
      (node (ref "U21") (pin "83") (pinfunction "VSS_83") (pintype "power_in"))
    )
    (net (code "208") (name "unconnected-(U21C-VSS-Pad94)") (class "Default")
      (node (ref "U21") (pin "94") (pinfunction "VSS_94") (pintype "power_in"))
    )
    (net (code "209") (name "unconnected-(U21C-VSS-Pad107)") (class "Default")
      (node (ref "U21") (pin "107") (pinfunction "VSS_107") (pintype "power_in"))
    )
    (net (code "210") (name "unconnected-(U21C-VSS-Pad120)") (class "Default")
      (node (ref "U21") (pin "120") (pinfunction "VSS_120") (pintype "power_in"))
    )
    (net (code "211") (name "unconnected-(U21C-VSS-Pad130)") (class "Default")
      (node (ref "U21") (pin "130") (pinfunction "VSS_130") (pintype "power_in"))
    )
    (net (code "212") (name "unconnected-(U21C-VSSA-Pad31)") (class "Default")
      (node (ref "U21") (pin "31") (pinfunction "VSSA_31") (pintype "power_in"))
    )
  )
)
